# Arm.net
KiCad netlist of a schematic drawn in EAGLE
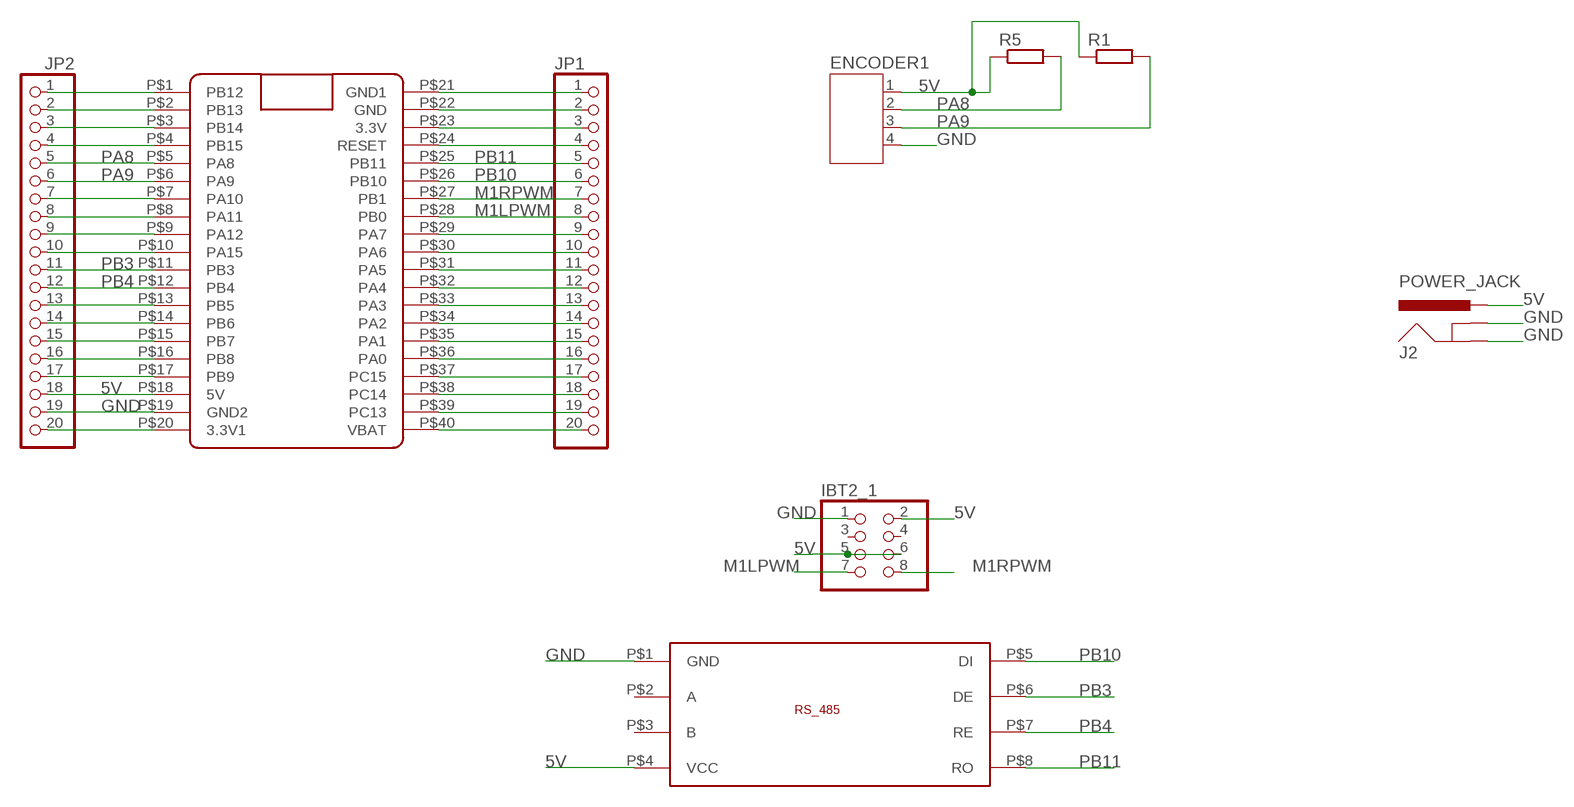
[diagram p0: schematic, sheet 1]

(export (version "E")
  (design (tool "Eeschema 10.0.6"))
  (components
    (comp (ref "ENCODER1")
      (value "JST-PH4")
      (footprint "eagle-import:JST-PH4")
      (libsource (lib "eagle-import") (part "JST-PH4"))
    )
    (comp (ref "IBT2_1")
      (value "PINHD-2X4")
      (footprint "eagle-import:2X04")
      (libsource (lib "eagle-import") (part "PINHD-2X4"))
    )
    (comp (ref "J2")
      (value "POWER_JACK")
      (footprint "eagle-import:POWER_JACK")
      (fields (field (name "MPN") "PJ-202A"))
      (libsource (lib "eagle-import") (part "POWER_JACK"))
    )
    (comp (ref "JP1")
      (value "PINHD-1X20")
      (footprint "eagle-import:1X20")
      (libsource (lib "eagle-import") (part "PINHD-1X20"))
    )
    (comp (ref "JP2")
      (value "PINHD-1X20")
      (footprint "eagle-import:1X20")
      (libsource (lib "eagle-import") (part "PINHD-1X20"))
    )
    (comp (ref "R1")
      (value "R-EU_0207/10")
      (footprint "eagle-import:0207_10")
      (libsource (lib "eagle-import") (part "R-EU_0207/10"))
    )
    (comp (ref "R5")
      (value "R-EU_0207/10")
      (footprint "eagle-import:0207_10")
      (libsource (lib "eagle-import") (part "R-EU_0207/10"))
    )
    (comp (ref "U$1")
      (value "BLUE_PILL")
      (footprint "eagle-import:BLUE_PILL")
      (libsource (lib "eagle-import") (part "BLUE_PILL"))
    )
    (comp (ref "U$2")
      (value "RS_485PCB")
      (footprint "eagle-import:RSS485PCB")
      (libsource (lib "eagle-import") (part "RS_485PCB"))
    )
  )
  (nets
    (net (code "1") (name "/5V") (class "Default")
      (node (ref "ENCODER1") (pin "1") (pinfunction "1_1") (pintype "passive"))
      (node (ref "IBT2_1") (pin "2") (pinfunction "2_2") (pintype "passive"))
      (node (ref "IBT2_1") (pin "5") (pinfunction "5_5") (pintype "passive"))
      (node (ref "IBT2_1") (pin "6") (pinfunction "6_6") (pintype "passive"))
      (node (ref "J2") (pin "PWR") (pinfunction "PWR_PWR") (pintype "bidirectional"))
      (node (ref "JP2") (pin "18") (pinfunction "18_18") (pintype "passive"))
      (node (ref "R1") (pin "1") (pinfunction "1_1") (pintype "passive"))
      (node (ref "R5") (pin "1") (pinfunction "1_1") (pintype "passive"))
      (node (ref "U$1") (pin "P$18") (pinfunction "5V_P$18") (pintype "bidirectional"))
      (node (ref "U$2") (pin "P$4") (pinfunction "VCC_P$4") (pintype "bidirectional"))
    )
    (net (code "2") (name "/GND") (class "Default")
      (node (ref "ENCODER1") (pin "4") (pinfunction "4_4") (pintype "passive"))
      (node (ref "IBT2_1") (pin "1") (pinfunction "1_1") (pintype "passive"))
      (node (ref "J2") (pin "GNDBREAK") (pinfunction "GNDBREAK_GNDBREAK") (pintype "bidirectional"))
      (node (ref "JP2") (pin "19") (pinfunction "19_19") (pintype "passive"))
      (node (ref "U$1") (pin "P$19") (pinfunction "GND2_P$19") (pintype "bidirectional"))
      (node (ref "U$2") (pin "P$1") (pinfunction "GND_P$1") (pintype "bidirectional"))
    )
    (net (code "3") (name "/M1LPWM") (class "Default")
      (node (ref "IBT2_1") (pin "7") (pinfunction "7_7") (pintype "passive"))
      (node (ref "JP1") (pin "8") (pinfunction "8_8") (pintype "passive"))
      (node (ref "U$1") (pin "P$28") (pinfunction "PB0_P$28") (pintype "bidirectional"))
    )
    (net (code "4") (name "/M1RPWM") (class "Default")
      (node (ref "IBT2_1") (pin "8") (pinfunction "8_8") (pintype "passive"))
      (node (ref "JP1") (pin "7") (pinfunction "7_7") (pintype "passive"))
      (node (ref "U$1") (pin "P$27") (pinfunction "PB1_P$27") (pintype "bidirectional"))
    )
    (net (code "5") (name "/PA8") (class "Default")
      (node (ref "ENCODER1") (pin "2") (pinfunction "2_2") (pintype "passive"))
      (node (ref "JP2") (pin "5") (pinfunction "5_5") (pintype "passive"))
      (node (ref "R5") (pin "2") (pinfunction "2_2") (pintype "passive"))
      (node (ref "U$1") (pin "P$5") (pinfunction "PA8_P$5") (pintype "bidirectional"))
    )
    (net (code "6") (name "/PA9") (class "Default")
      (node (ref "ENCODER1") (pin "3") (pinfunction "3_3") (pintype "passive"))
      (node (ref "JP2") (pin "6") (pinfunction "6_6") (pintype "passive"))
      (node (ref "R1") (pin "2") (pinfunction "2_2") (pintype "passive"))
      (node (ref "U$1") (pin "P$6") (pinfunction "PA9_P$6") (pintype "bidirectional"))
    )
    (net (code "7") (name "/PB3") (class "Default")
      (node (ref "JP2") (pin "11") (pinfunction "11_11") (pintype "passive"))
      (node (ref "U$1") (pin "P$11") (pinfunction "PB3_P$11") (pintype "bidirectional"))
      (node (ref "U$2") (pin "P$6") (pinfunction "DE_P$6") (pintype "bidirectional"))
    )
    (net (code "8") (name "/PB4") (class "Default")
      (node (ref "JP2") (pin "12") (pinfunction "12_12") (pintype "passive"))
      (node (ref "U$1") (pin "P$12") (pinfunction "PB4_P$12") (pintype "bidirectional"))
      (node (ref "U$2") (pin "P$7") (pinfunction "RE_P$7") (pintype "bidirectional"))
    )
    (net (code "9") (name "/PB10") (class "Default")
      (node (ref "JP1") (pin "6") (pinfunction "6_6") (pintype "passive"))
      (node (ref "U$1") (pin "P$26") (pinfunction "PB10_P$26") (pintype "bidirectional"))
      (node (ref "U$2") (pin "P$5") (pinfunction "DI_P$5") (pintype "bidirectional"))
    )
    (net (code "10") (name "/PB11") (class "Default")
      (node (ref "JP1") (pin "5") (pinfunction "5_5") (pintype "passive"))
      (node (ref "U$1") (pin "P$25") (pinfunction "PB11_P$25") (pintype "bidirectional"))
      (node (ref "U$2") (pin "P$8") (pinfunction "RO_P$8") (pintype "bidirectional"))
    )
    (net (code "11") (name "Net-(U$1-3.3V)") (class "Default")
      (node (ref "JP1") (pin "3") (pinfunction "3_3") (pintype "passive"))
      (node (ref "U$1") (pin "P$23") (pinfunction "3.3V_P$23") (pintype "bidirectional"))
    )
    (net (code "12") (name "Net-(U$1-3.3V1)") (class "Default")
      (node (ref "JP2") (pin "20") (pinfunction "20_20") (pintype "passive"))
      (node (ref "U$1") (pin "P$20") (pinfunction "3.3V1_P$20") (pintype "bidirectional"))
    )
    (net (code "13") (name "Net-(U$1-GND)") (class "Default")
      (node (ref "JP1") (pin "2") (pinfunction "2_2") (pintype "passive"))
      (node (ref "U$1") (pin "P$22") (pinfunction "GND_P$22") (pintype "bidirectional"))
    )
    (net (code "14") (name "Net-(U$1-GND1)") (class "Default")
      (node (ref "JP1") (pin "1") (pinfunction "1_1") (pintype "passive"))
      (node (ref "U$1") (pin "P$21") (pinfunction "GND1_P$21") (pintype "power_in"))
    )
    (net (code "15") (name "Net-(U$1-PA0)") (class "Default")
      (node (ref "JP1") (pin "16") (pinfunction "16_16") (pintype "passive"))
      (node (ref "U$1") (pin "P$36") (pinfunction "PA0_P$36") (pintype "bidirectional"))
    )
    (net (code "16") (name "Net-(U$1-PA1)") (class "Default")
      (node (ref "JP1") (pin "15") (pinfunction "15_15") (pintype "passive"))
      (node (ref "U$1") (pin "P$35") (pinfunction "PA1_P$35") (pintype "bidirectional"))
    )
    (net (code "17") (name "Net-(U$1-PA2)") (class "Default")
      (node (ref "JP1") (pin "14") (pinfunction "14_14") (pintype "passive"))
      (node (ref "U$1") (pin "P$34") (pinfunction "PA2_P$34") (pintype "bidirectional"))
    )
    (net (code "18") (name "Net-(U$1-PA3)") (class "Default")
      (node (ref "JP1") (pin "13") (pinfunction "13_13") (pintype "passive"))
      (node (ref "U$1") (pin "P$33") (pinfunction "PA3_P$33") (pintype "bidirectional"))
    )
    (net (code "19") (name "Net-(U$1-PA4)") (class "Default")
      (node (ref "JP1") (pin "12") (pinfunction "12_12") (pintype "passive"))
      (node (ref "U$1") (pin "P$32") (pinfunction "PA4_P$32") (pintype "bidirectional"))
    )
    (net (code "20") (name "Net-(U$1-PA5)") (class "Default")
      (node (ref "JP1") (pin "11") (pinfunction "11_11") (pintype "passive"))
      (node (ref "U$1") (pin "P$31") (pinfunction "PA5_P$31") (pintype "bidirectional"))
    )
    (net (code "21") (name "Net-(U$1-PA6)") (class "Default")
      (node (ref "JP1") (pin "10") (pinfunction "10_10") (pintype "passive"))
      (node (ref "U$1") (pin "P$30") (pinfunction "PA6_P$30") (pintype "bidirectional"))
    )
    (net (code "22") (name "Net-(U$1-PA7)") (class "Default")
      (node (ref "JP1") (pin "9") (pinfunction "9_9") (pintype "passive"))
      (node (ref "U$1") (pin "P$29") (pinfunction "PA7_P$29") (pintype "bidirectional"))
    )
    (net (code "23") (name "Net-(U$1-PA10)") (class "Default")
      (node (ref "JP2") (pin "7") (pinfunction "7_7") (pintype "passive"))
      (node (ref "U$1") (pin "P$7") (pinfunction "PA10_P$7") (pintype "bidirectional"))
    )
    (net (code "24") (name "Net-(U$1-PA11)") (class "Default")
      (node (ref "JP2") (pin "8") (pinfunction "8_8") (pintype "passive"))
      (node (ref "U$1") (pin "P$8") (pinfunction "PA11_P$8") (pintype "bidirectional"))
    )
    (net (code "25") (name "Net-(U$1-PA12)") (class "Default")
      (node (ref "JP2") (pin "9") (pinfunction "9_9") (pintype "passive"))
      (node (ref "U$1") (pin "P$9") (pinfunction "PA12_P$9") (pintype "bidirectional"))
    )
    (net (code "26") (name "Net-(U$1-PA15)") (class "Default")
      (node (ref "JP2") (pin "10") (pinfunction "10_10") (pintype "passive"))
      (node (ref "U$1") (pin "P$10") (pinfunction "PA15_P$10") (pintype "bidirectional"))
    )
    (net (code "27") (name "Net-(U$1-PB5)") (class "Default")
      (node (ref "JP2") (pin "13") (pinfunction "13_13") (pintype "passive"))
      (node (ref "U$1") (pin "P$13") (pinfunction "PB5_P$13") (pintype "bidirectional"))
    )
    (net (code "28") (name "Net-(U$1-PB6)") (class "Default")
      (node (ref "JP2") (pin "14") (pinfunction "14_14") (pintype "passive"))
      (node (ref "U$1") (pin "P$14") (pinfunction "PB6_P$14") (pintype "bidirectional"))
    )
    (net (code "29") (name "Net-(U$1-PB7)") (class "Default")
      (node (ref "JP2") (pin "15") (pinfunction "15_15") (pintype "passive"))
      (node (ref "U$1") (pin "P$15") (pinfunction "PB7_P$15") (pintype "bidirectional"))
    )
    (net (code "30") (name "Net-(U$1-PB8)") (class "Default")
      (node (ref "JP2") (pin "16") (pinfunction "16_16") (pintype "passive"))
      (node (ref "U$1") (pin "P$16") (pinfunction "PB8_P$16") (pintype "bidirectional"))
    )
    (net (code "31") (name "Net-(U$1-PB9)") (class "Default")
      (node (ref "JP2") (pin "17") (pinfunction "17_17") (pintype "passive"))
      (node (ref "U$1") (pin "P$17") (pinfunction "PB9_P$17") (pintype "bidirectional"))
    )
    (net (code "32") (name "Net-(U$1-PB12)") (class "Default")
      (node (ref "JP2") (pin "1") (pinfunction "1_1") (pintype "passive"))
      (node (ref "U$1") (pin "P$1") (pinfunction "PB12_P$1") (pintype "bidirectional"))
    )
    (net (code "33") (name "Net-(U$1-PB13)") (class "Default")
      (node (ref "JP2") (pin "2") (pinfunction "2_2") (pintype "passive"))
      (node (ref "U$1") (pin "P$2") (pinfunction "PB13_P$2") (pintype "bidirectional"))
    )
    (net (code "34") (name "Net-(U$1-PB14)") (class "Default")
      (node (ref "JP2") (pin "3") (pinfunction "3_3") (pintype "passive"))
      (node (ref "U$1") (pin "P$3") (pinfunction "PB14_P$3") (pintype "bidirectional"))
    )
    (net (code "35") (name "Net-(U$1-PB15)") (class "Default")
      (node (ref "JP2") (pin "4") (pinfunction "4_4") (pintype "passive"))
      (node (ref "U$1") (pin "P$4") (pinfunction "PB15_P$4") (pintype "bidirectional"))
    )
    (net (code "36") (name "Net-(U$1-PC13)") (class "Default")
      (node (ref "JP1") (pin "19") (pinfunction "19_19") (pintype "passive"))
      (node (ref "U$1") (pin "P$39") (pinfunction "PC13_P$39") (pintype "bidirectional"))
    )
    (net (code "37") (name "Net-(U$1-PC14)") (class "Default")
      (node (ref "JP1") (pin "18") (pinfunction "18_18") (pintype "passive"))
      (node (ref "U$1") (pin "P$38") (pinfunction "PC14_P$38") (pintype "bidirectional"))
    )
    (net (code "38") (name "Net-(U$1-PC15)") (class "Default")
      (node (ref "JP1") (pin "17") (pinfunction "17_17") (pintype "passive"))
      (node (ref "U$1") (pin "P$37") (pinfunction "PC15_P$37") (pintype "bidirectional"))
    )
    (net (code "39") (name "Net-(U$1-RESET)") (class "Default")
      (node (ref "JP1") (pin "4") (pinfunction "4_4") (pintype "passive"))
      (node (ref "U$1") (pin "P$24") (pinfunction "RESET_P$24") (pintype "bidirectional"))
    )
    (net (code "40") (name "Net-(U$1-VBAT)") (class "Default")
      (node (ref "JP1") (pin "20") (pinfunction "20_20") (pintype "passive"))
      (node (ref "U$1") (pin "P$40") (pinfunction "VBAT_P$40") (pintype "bidirectional"))
    )
    (net (code "41") (name "unconnected-(IBT2_1-Pad3)") (class "Default")
      (node (ref "IBT2_1") (pin "3") (pinfunction "3_3") (pintype "passive"))
    )
    (net (code "42") (name "unconnected-(IBT2_1-Pad4)") (class "Default")
      (node (ref "IBT2_1") (pin "4") (pinfunction "4_4") (pintype "passive"))
    )
    (net (code "43") (name "unconnected-(J2-PadGND)") (class "Default")
      (node (ref "J2") (pin "GND") (pinfunction "GND_GND") (pintype "bidirectional"))
    )
    (net (code "44") (name "unconnected-(U$2-A-PadP$2)") (class "Default")
      (node (ref "U$2") (pin "P$2") (pinfunction "A_P$2") (pintype "bidirectional"))
    )
    (net (code "45") (name "unconnected-(U$2-B-PadP$3)") (class "Default")
      (node (ref "U$2") (pin "P$3") (pinfunction "B_P$3") (pintype "bidirectional"))
    )
  )
)
